# Bracelet.net
KiCad netlist of a schematic drawn in EAGLE
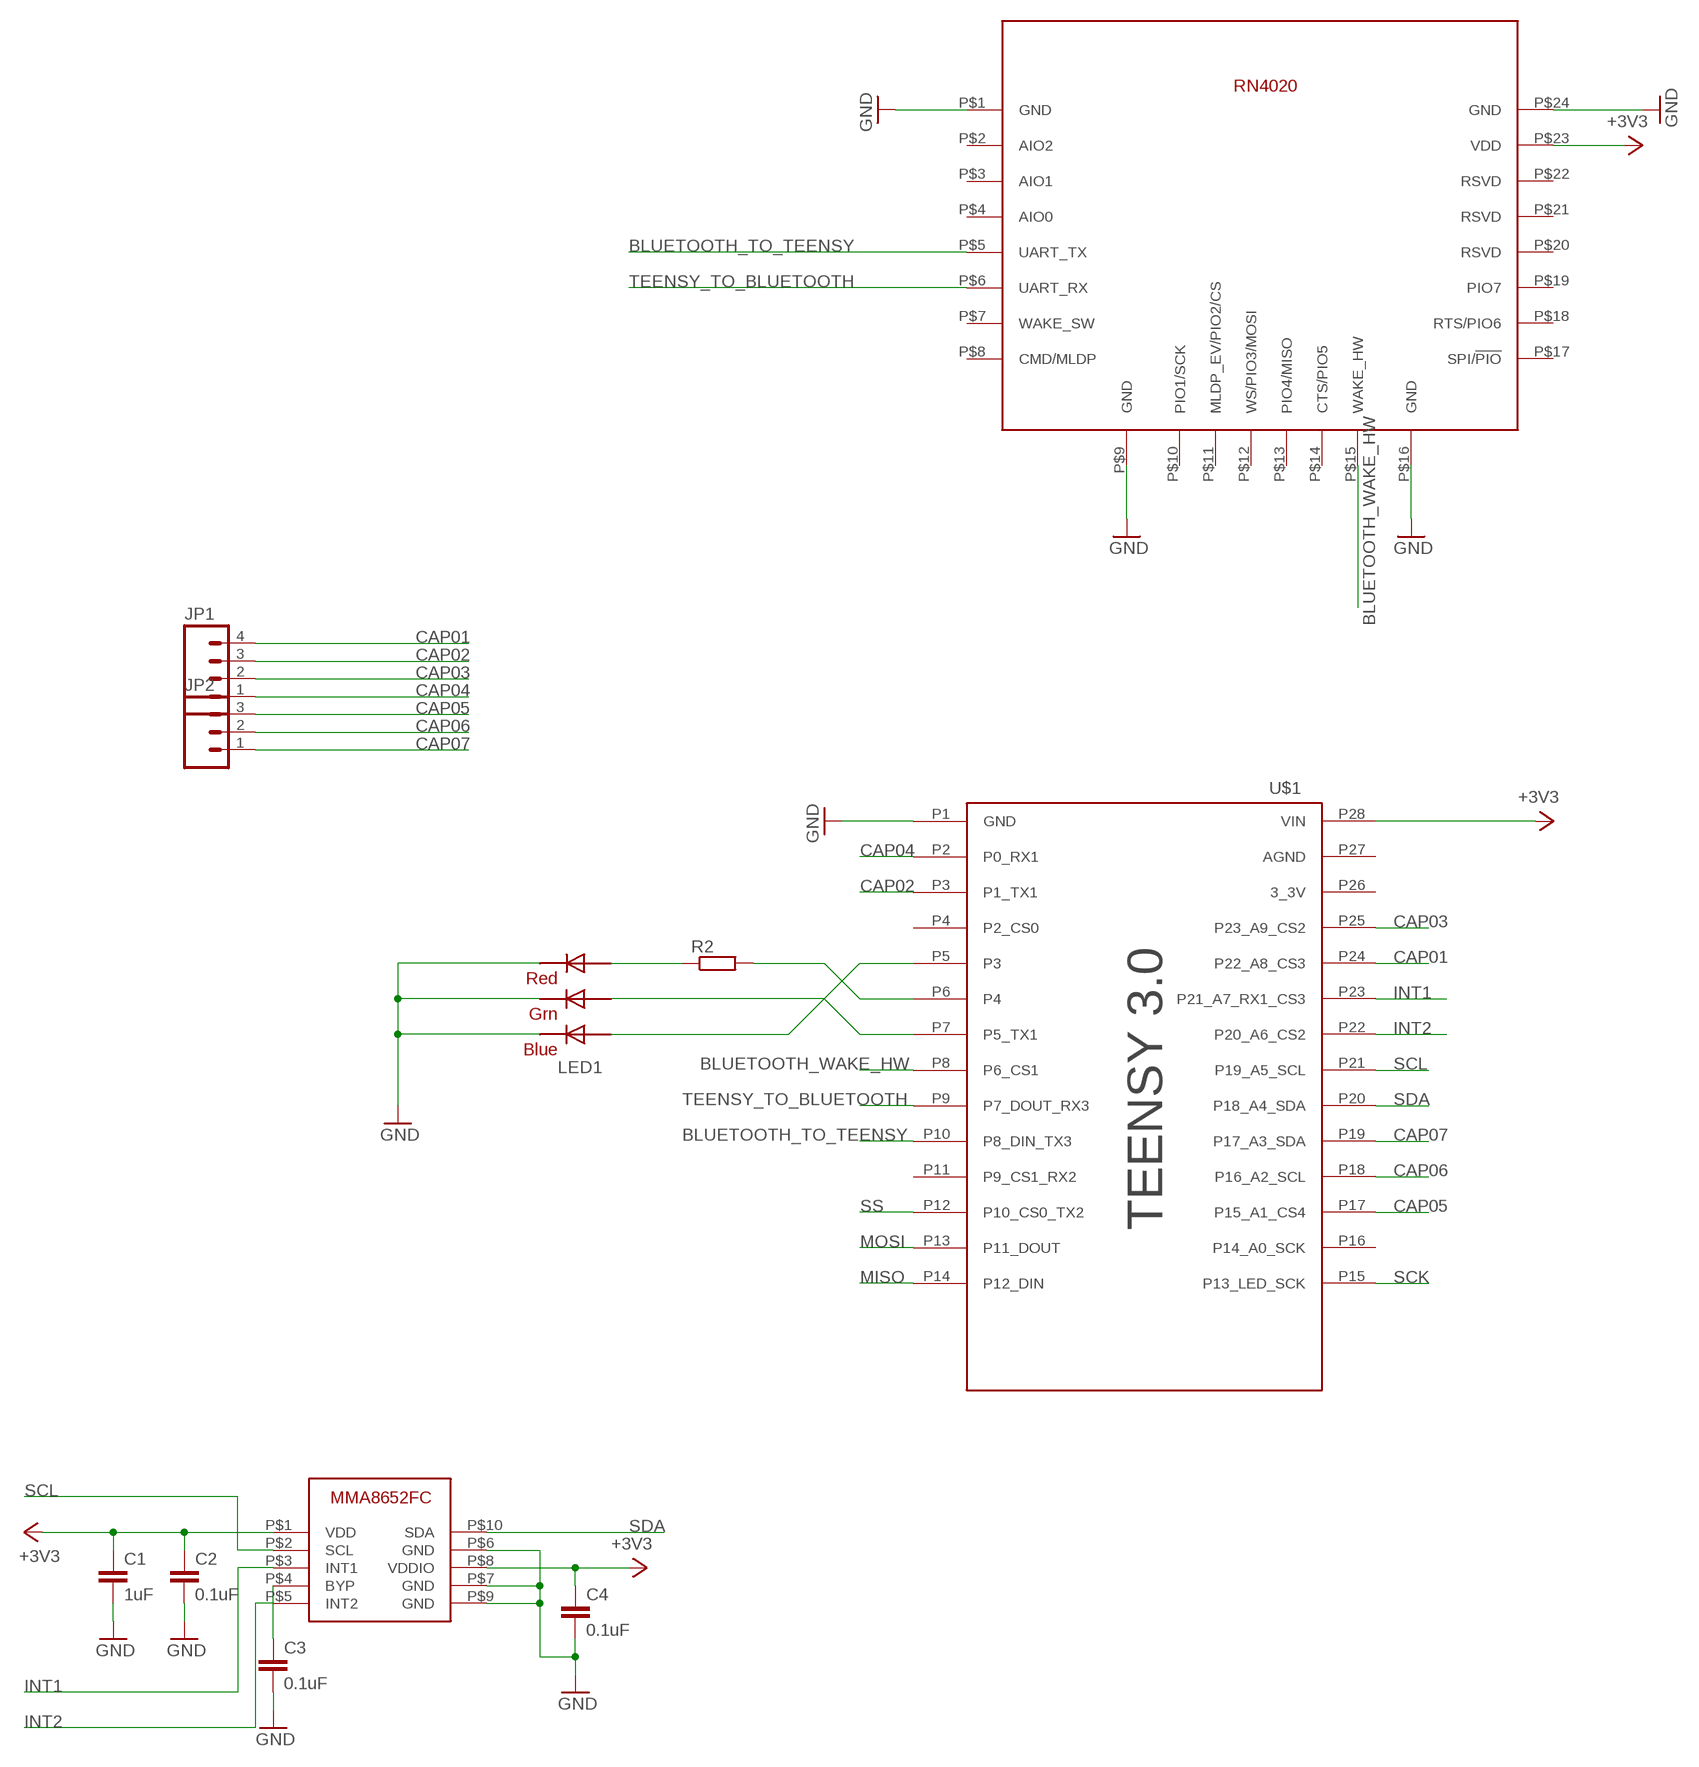
[diagram p0: schematic, sheet 1]

(export (version "E")
  (design (tool "Eeschema 10.0.6"))
  (components
    (comp (ref "C1")
      (value "1uF")
      (footprint "eagle-import:C0805")
      (libsource (lib "eagle-import") (part "C-EUC0805"))
    )
    (comp (ref "C2")
      (value "0.1uF")
      (footprint "eagle-import:C0805")
      (libsource (lib "eagle-import") (part "C-EUC0805"))
    )
    (comp (ref "C3")
      (value "0.1uF")
      (footprint "eagle-import:C0805")
      (libsource (lib "eagle-import") (part "C-EUC0805"))
    )
    (comp (ref "C4")
      (value "0.1uF")
      (footprint "eagle-import:C0805")
      (libsource (lib "eagle-import") (part "C-EUC0805"))
    )
    (comp (ref "JP1")
      (value "M04PTH")
      (footprint "eagle-import:1X04")
      (libsource (lib "eagle-import") (part "M04PTH"))
    )
    (comp (ref "JP2")
      (value "M03PTH")
      (footprint "eagle-import:1X03")
      (libsource (lib "eagle-import") (part "M03PTH"))
    )
    (comp (ref "LED1")
      (value "RGBLED5050")
      (footprint "eagle-import:RGBLED5050")
      (libsource (lib "eagle-import") (part "RGBLED5050"))
    )
    (comp (ref "R2")
      (value "R-EU_R0805")
      (footprint "eagle-import:R0805")
      (libsource (lib "eagle-import") (part "R-EU_R0805"))
    )
    (comp (ref "RN4020")
      (value "RN4020")
      (footprint "eagle-import:RN4020")
      (libsource (lib "eagle-import") (part "RN4020"))
    )
    (comp (ref "U$1")
      (value "TEENSY3")
      (footprint "eagle-import:TEENSY3_BRD")
      (libsource (lib "eagle-import") (part "TEENSY3"))
    )
    (comp (ref "U$3")
      (value "MMA8652FC")
      (footprint "eagle-import:MMA8652FC")
      (libsource (lib "eagle-import") (part "MMA8652FC"))
    )
  )
  (nets
    (net (code "1") (name "+3V3") (class "Default")
      (node (ref "C1") (pin "1") (pinfunction "1_1") (pintype "passive"))
      (node (ref "C2") (pin "1") (pinfunction "1_1") (pintype "passive"))
      (node (ref "C4") (pin "1") (pinfunction "1_1") (pintype "passive"))
      (node (ref "RN4020") (pin "P$23") (pinfunction "VDD_P$23") (pintype "power_in"))
      (node (ref "U$1") (pin "P28") (pinfunction "VIN_P28") (pintype "bidirectional"))
      (node (ref "U$3") (pin "P$1") (pinfunction "VDD_P$1") (pintype "power_in"))
      (node (ref "U$3") (pin "P$8") (pinfunction "VDDIO_P$8") (pintype "power_in"))
    )
    (net (code "2") (name "/BLUETOOTH_TO_TEENSY") (class "Default")
      (node (ref "RN4020") (pin "P$5") (pinfunction "UART_TX_P$5") (pintype "output"))
      (node (ref "U$1") (pin "P10") (pinfunction "P8_DIN_TX3_P10") (pintype "bidirectional"))
    )
    (net (code "3") (name "/BLUETOOTH_WAKE_HW") (class "Default")
      (node (ref "RN4020") (pin "P$15") (pinfunction "WAKE_HW_P$15") (pintype "bidirectional"))
      (node (ref "U$1") (pin "P8") (pinfunction "P6_CS1_P8") (pintype "bidirectional"))
    )
    (net (code "4") (name "/CAP01") (class "Default")
      (node (ref "JP1") (pin "4") (pinfunction "4_4") (pintype "passive"))
      (node (ref "U$1") (pin "P24") (pinfunction "P22_A8_CS3_P24") (pintype "bidirectional"))
    )
    (net (code "5") (name "/CAP02") (class "Default")
      (node (ref "JP1") (pin "3") (pinfunction "3_3") (pintype "passive"))
      (node (ref "U$1") (pin "P3") (pinfunction "P1_TX1_P3") (pintype "bidirectional"))
    )
    (net (code "6") (name "/CAP03") (class "Default")
      (node (ref "JP1") (pin "2") (pinfunction "2_2") (pintype "passive"))
      (node (ref "U$1") (pin "P25") (pinfunction "P23_A9_CS2_P25") (pintype "bidirectional"))
    )
    (net (code "7") (name "/CAP04") (class "Default")
      (node (ref "JP1") (pin "1") (pinfunction "1_1") (pintype "passive"))
      (node (ref "U$1") (pin "P2") (pinfunction "P0_RX1_P2") (pintype "bidirectional"))
    )
    (net (code "8") (name "/CAP05") (class "Default")
      (node (ref "JP2") (pin "3") (pinfunction "3_3") (pintype "passive"))
      (node (ref "U$1") (pin "P17") (pinfunction "P15_A1_CS4_P17") (pintype "bidirectional"))
    )
    (net (code "9") (name "/CAP06") (class "Default")
      (node (ref "JP2") (pin "2") (pinfunction "2_2") (pintype "passive"))
      (node (ref "U$1") (pin "P18") (pinfunction "P16_A2_SCL_P18") (pintype "bidirectional"))
    )
    (net (code "10") (name "/CAP07") (class "Default")
      (node (ref "JP2") (pin "1") (pinfunction "1_1") (pintype "passive"))
      (node (ref "U$1") (pin "P19") (pinfunction "P17_A3_SDA_P19") (pintype "bidirectional"))
    )
    (net (code "11") (name "/INT1") (class "Default")
      (node (ref "U$1") (pin "P23") (pinfunction "P21_A7_RX1_CS3_P23") (pintype "bidirectional"))
      (node (ref "U$3") (pin "P$3") (pinfunction "INT1_P$3") (pintype "output"))
    )
    (net (code "12") (name "/INT2") (class "Default")
      (node (ref "U$1") (pin "P22") (pinfunction "P20_A6_CS2_P22") (pintype "bidirectional"))
      (node (ref "U$3") (pin "P$5") (pinfunction "INT2_P$5") (pintype "output"))
    )
    (net (code "13") (name "/MISO") (class "Default")
      (node (ref "U$1") (pin "P14") (pinfunction "P12_DIN_P14") (pintype "bidirectional"))
    )
    (net (code "14") (name "/MOSI") (class "Default")
      (node (ref "U$1") (pin "P13") (pinfunction "P11_DOUT_P13") (pintype "bidirectional"))
    )
    (net (code "15") (name "/SCK") (class "Default")
      (node (ref "U$1") (pin "P15") (pinfunction "P13_LED_SCK_P15") (pintype "bidirectional"))
    )
    (net (code "16") (name "/SCL") (class "Default")
      (node (ref "U$1") (pin "P21") (pinfunction "P19_A5_SCL_P21") (pintype "bidirectional"))
      (node (ref "U$3") (pin "P$2") (pinfunction "SCL_P$2") (pintype "bidirectional"))
    )
    (net (code "17") (name "/SDA") (class "Default")
      (node (ref "U$1") (pin "P20") (pinfunction "P18_A4_SDA_P20") (pintype "bidirectional"))
      (node (ref "U$3") (pin "P$10") (pinfunction "SDA_P$10") (pintype "bidirectional"))
    )
    (net (code "18") (name "/SS") (class "Default")
      (node (ref "U$1") (pin "P12") (pinfunction "P10_CS0_TX2_P12") (pintype "bidirectional"))
    )
    (net (code "19") (name "/TEENSY_TO_BLUETOOTH") (class "Default")
      (node (ref "RN4020") (pin "P$6") (pinfunction "UART_RX_P$6") (pintype "input"))
      (node (ref "U$1") (pin "P9") (pinfunction "P7_DOUT_RX3_P9") (pintype "bidirectional"))
    )
    (net (code "20") (name "GND") (class "Default")
      (node (ref "C1") (pin "2") (pinfunction "2_2") (pintype "passive"))
      (node (ref "C2") (pin "2") (pinfunction "2_2") (pintype "passive"))
      (node (ref "C3") (pin "2") (pinfunction "2_2") (pintype "passive"))
      (node (ref "C4") (pin "2") (pinfunction "2_2") (pintype "passive"))
      (node (ref "LED1") (pin "4") (pinfunction "BLUE_C_4") (pintype "bidirectional"))
      (node (ref "LED1") (pin "5") (pinfunction "RED_C_5") (pintype "bidirectional"))
      (node (ref "LED1") (pin "6") (pinfunction "GREEN_C_6") (pintype "bidirectional"))
      (node (ref "RN4020") (pin "P$1") (pinfunction "GND_P$1") (pintype "power_in"))
      (node (ref "RN4020") (pin "P$16") (pinfunction "GND_P$16") (pintype "power_in"))
      (node (ref "RN4020") (pin "P$24") (pinfunction "GND_P$24") (pintype "power_in"))
      (node (ref "RN4020") (pin "P$9") (pinfunction "GND_P$9") (pintype "power_in"))
      (node (ref "U$1") (pin "P1") (pinfunction "GND_P1") (pintype "bidirectional"))
      (node (ref "U$3") (pin "P$6") (pinfunction "GND_P$6") (pintype "power_in"))
      (node (ref "U$3") (pin "P$7") (pinfunction "GND_P$7") (pintype "power_in"))
      (node (ref "U$3") (pin "P$9") (pinfunction "GND_P$9") (pintype "power_in"))
    )
    (net (code "21") (name "Net-(LED1-BLUE_A)") (class "Default")
      (node (ref "LED1") (pin "3") (pinfunction "BLUE_A_3") (pintype "bidirectional"))
      (node (ref "U$1") (pin "P5") (pinfunction "P3_P5") (pintype "bidirectional"))
    )
    (net (code "22") (name "Net-(LED1-GREEN_A)") (class "Default")
      (node (ref "LED1") (pin "1") (pinfunction "GREEN_A_1") (pintype "bidirectional"))
      (node (ref "U$1") (pin "P7") (pinfunction "P5_TX1_P7") (pintype "bidirectional"))
    )
    (net (code "23") (name "Net-(LED1-RED_A)") (class "Default")
      (node (ref "LED1") (pin "2") (pinfunction "RED_A_2") (pintype "bidirectional"))
      (node (ref "R2") (pin "1") (pinfunction "1_1") (pintype "passive"))
    )
    (net (code "24") (name "Net-(U$1-P4)") (class "Default")
      (node (ref "R2") (pin "2") (pinfunction "2_2") (pintype "passive"))
      (node (ref "U$1") (pin "P6") (pinfunction "P4_P6") (pintype "bidirectional"))
    )
    (net (code "25") (name "Net-(U$3-BYP)") (class "Default")
      (node (ref "C3") (pin "1") (pinfunction "1_1") (pintype "passive"))
      (node (ref "U$3") (pin "P$4") (pinfunction "BYP_P$4") (pintype "output"))
    )
    (net (code "26") (name "unconnected-(RN4020-AIO0-PadP$4)") (class "Default")
      (node (ref "RN4020") (pin "P$4") (pinfunction "AIO0_P$4") (pintype "bidirectional"))
    )
    (net (code "27") (name "unconnected-(RN4020-AIO1-PadP$3)") (class "Default")
      (node (ref "RN4020") (pin "P$3") (pinfunction "AIO1_P$3") (pintype "bidirectional"))
    )
    (net (code "28") (name "unconnected-(RN4020-AIO2-PadP$2)") (class "Default")
      (node (ref "RN4020") (pin "P$2") (pinfunction "AIO2_P$2") (pintype "bidirectional"))
    )
    (net (code "29") (name "unconnected-(RN4020-CMD{slash}MLDP-PadP$8)") (class "Default")
      (node (ref "RN4020") (pin "P$8") (pinfunction "CMD/MLDP_P$8") (pintype "input"))
    )
    (net (code "30") (name "unconnected-(RN4020-CTS{slash}PIO5-PadP$14)") (class "Default")
      (node (ref "RN4020") (pin "P$14") (pinfunction "CTS/PIO5_P$14") (pintype "bidirectional"))
    )
    (net (code "31") (name "unconnected-(RN4020-MLDP_EV{slash}PIO2{slash}CS-PadP$11)") (class "Default")
      (node (ref "RN4020") (pin "P$11") (pinfunction "MLDP_EV/PIO2/CS_P$11") (pintype "bidirectional"))
    )
    (net (code "32") (name "unconnected-(RN4020-PIO1{slash}SCK-PadP$10)") (class "Default")
      (node (ref "RN4020") (pin "P$10") (pinfunction "PIO1/SCK_P$10") (pintype "bidirectional"))
    )
    (net (code "33") (name "unconnected-(RN4020-PIO4{slash}MISO-PadP$13)") (class "Default")
      (node (ref "RN4020") (pin "P$13") (pinfunction "PIO4/MISO_P$13") (pintype "bidirectional"))
    )
    (net (code "34") (name "unconnected-(RN4020-PIO7-PadP$19)") (class "Default")
      (node (ref "RN4020") (pin "P$19") (pinfunction "PIO7_P$19") (pintype "bidirectional"))
    )
    (net (code "35") (name "unconnected-(RN4020-RSVD-PadP$20)") (class "Default")
      (node (ref "RN4020") (pin "P$20") (pinfunction "RSVD_P$20") (pintype "no_connect"))
    )
    (net (code "36") (name "unconnected-(RN4020-RSVD-PadP$21)") (class "Default")
      (node (ref "RN4020") (pin "P$21") (pinfunction "RSVD_P$21") (pintype "no_connect"))
    )
    (net (code "37") (name "unconnected-(RN4020-RSVD-PadP$22)") (class "Default")
      (node (ref "RN4020") (pin "P$22") (pinfunction "RSVD_P$22") (pintype "no_connect"))
    )
    (net (code "38") (name "unconnected-(RN4020-RTS{slash}PIO6-PadP$18)") (class "Default")
      (node (ref "RN4020") (pin "P$18") (pinfunction "RTS/PIO6_P$18") (pintype "bidirectional"))
    )
    (net (code "39") (name "unconnected-(RN4020-SPI{slash}~{PIO}-PadP$17)") (class "Default")
      (node (ref "RN4020") (pin "P$17") (pinfunction "SPI/~{PIO}_P$17") (pintype "input"))
    )
    (net (code "40") (name "unconnected-(RN4020-WAKE_SW-PadP$7)") (class "Default")
      (node (ref "RN4020") (pin "P$7") (pinfunction "WAKE_SW_P$7") (pintype "input"))
    )
    (net (code "41") (name "unconnected-(RN4020-WS{slash}PIO3{slash}MOSI-PadP$12)") (class "Default")
      (node (ref "RN4020") (pin "P$12") (pinfunction "WS/PIO3/MOSI_P$12") (pintype "bidirectional"))
    )
    (net (code "42") (name "unconnected-(U$1-3_3V-PadP26)") (class "Default")
      (node (ref "U$1") (pin "P26") (pinfunction "3_3V_P26") (pintype "bidirectional"))
    )
    (net (code "43") (name "unconnected-(U$1-AGND-PadP27)") (class "Default")
      (node (ref "U$1") (pin "P27") (pinfunction "AGND_P27") (pintype "bidirectional"))
    )
    (net (code "44") (name "unconnected-(U$1-P2_CS0-PadP4)") (class "Default")
      (node (ref "U$1") (pin "P4") (pinfunction "P2_CS0_P4") (pintype "bidirectional"))
    )
    (net (code "45") (name "unconnected-(U$1-P9_CS1_RX2-PadP11)") (class "Default")
      (node (ref "U$1") (pin "P11") (pinfunction "P9_CS1_RX2_P11") (pintype "bidirectional"))
    )
    (net (code "46") (name "unconnected-(U$1-P14_A0_SCK-PadP16)") (class "Default")
      (node (ref "U$1") (pin "P16") (pinfunction "P14_A0_SCK_P16") (pintype "bidirectional"))
    )
  )
)
